# StepperMotor-Shield-ArduinoUNO.net
KiCad netlist of a schematic drawn in EAGLE
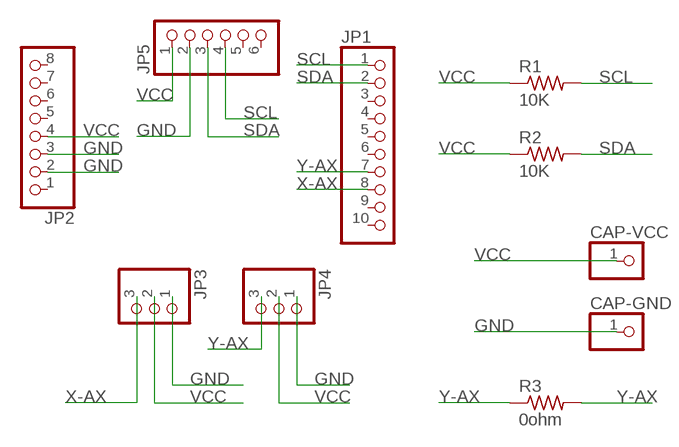
[diagram p0: schematic, sheet 1]

(export (version "E")
  (design (tool "Eeschema 10.0.6"))
  (components
    (comp (ref "CAP-GND")
      (value "PINHD-1X1")
      (footprint "eagle-import:1X01")
      (libsource (lib "eagle-import") (part "PINHD-1X1"))
    )
    (comp (ref "CAP-VCC")
      (value "PINHD-1X1")
      (footprint "eagle-import:1X01")
      (libsource (lib "eagle-import") (part "PINHD-1X1"))
    )
    (comp (ref "JP1")
      (value "PINHD-1X10")
      (footprint "eagle-import:1X10")
      (libsource (lib "eagle-import") (part "PINHD-1X10"))
    )
    (comp (ref "JP2")
      (value "PINHD-1X8")
      (footprint "eagle-import:1X08")
      (libsource (lib "eagle-import") (part "PINHD-1X8"))
    )
    (comp (ref "JP3")
      (value "PINHD-1X3")
      (footprint "eagle-import:1X03")
      (libsource (lib "eagle-import") (part "PINHD-1X3"))
    )
    (comp (ref "JP4")
      (value "PINHD-1X3")
      (footprint "eagle-import:1X03")
      (libsource (lib "eagle-import") (part "PINHD-1X3"))
    )
    (comp (ref "JP5")
      (value "PINHD-1X6")
      (footprint "eagle-import:1X06")
      (libsource (lib "eagle-import") (part "PINHD-1X6"))
    )
    (comp (ref "R1")
      (value "10K")
      (footprint "eagle-import:R1206FAB")
      (libsource (lib "eagle-import") (part "RES-US1206FAB"))
    )
    (comp (ref "R2")
      (value "10K")
      (footprint "eagle-import:R1206FAB")
      (libsource (lib "eagle-import") (part "RES-US1206FAB"))
    )
    (comp (ref "R3")
      (value "0ohm")
      (footprint "eagle-import:R1206FAB")
      (libsource (lib "eagle-import") (part "RES-US1206FAB"))
    )
  )
  (nets
    (net (code "1") (name "/GND") (class "Default")
      (node (ref "CAP-GND") (pin "1") (pinfunction "1_1") (pintype "passive"))
      (node (ref "JP2") (pin "2") (pinfunction "2_2") (pintype "passive"))
      (node (ref "JP2") (pin "3") (pinfunction "3_3") (pintype "passive"))
      (node (ref "JP3") (pin "1") (pinfunction "1_1") (pintype "passive"))
      (node (ref "JP4") (pin "1") (pinfunction "1_1") (pintype "passive"))
      (node (ref "JP5") (pin "2") (pinfunction "2_2") (pintype "passive"))
    )
    (net (code "2") (name "/SCL") (class "Default")
      (node (ref "JP1") (pin "1") (pinfunction "1_1") (pintype "passive"))
      (node (ref "JP5") (pin "4") (pinfunction "4_4") (pintype "passive"))
      (node (ref "R1") (pin "2") (pinfunction "2_2") (pintype "passive"))
    )
    (net (code "3") (name "/SDA") (class "Default")
      (node (ref "JP1") (pin "2") (pinfunction "2_2") (pintype "passive"))
      (node (ref "JP5") (pin "3") (pinfunction "3_3") (pintype "passive"))
      (node (ref "R2") (pin "2") (pinfunction "2_2") (pintype "passive"))
    )
    (net (code "4") (name "/VCC") (class "Default")
      (node (ref "CAP-VCC") (pin "1") (pinfunction "1_1") (pintype "passive"))
      (node (ref "JP2") (pin "4") (pinfunction "4_4") (pintype "passive"))
      (node (ref "JP3") (pin "2") (pinfunction "2_2") (pintype "passive"))
      (node (ref "JP4") (pin "2") (pinfunction "2_2") (pintype "passive"))
      (node (ref "JP5") (pin "1") (pinfunction "1_1") (pintype "passive"))
      (node (ref "R1") (pin "1") (pinfunction "1_1") (pintype "passive"))
      (node (ref "R2") (pin "1") (pinfunction "1_1") (pintype "passive"))
    )
    (net (code "5") (name "/X-AX") (class "Default")
      (node (ref "JP1") (pin "8") (pinfunction "8_8") (pintype "passive"))
      (node (ref "JP3") (pin "3") (pinfunction "3_3") (pintype "passive"))
    )
    (net (code "6") (name "/Y-AX") (class "Default")
      (node (ref "JP1") (pin "7") (pinfunction "7_7") (pintype "passive"))
      (node (ref "JP4") (pin "3") (pinfunction "3_3") (pintype "passive"))
      (node (ref "R3") (pin "1") (pinfunction "1_1") (pintype "passive"))
      (node (ref "R3") (pin "2") (pinfunction "2_2") (pintype "passive"))
    )
    (net (code "7") (name "unconnected-(JP1-Pad3)") (class "Default")
      (node (ref "JP1") (pin "3") (pinfunction "3_3") (pintype "passive"))
    )
    (net (code "8") (name "unconnected-(JP1-Pad4)") (class "Default")
      (node (ref "JP1") (pin "4") (pinfunction "4_4") (pintype "passive"))
    )
    (net (code "9") (name "unconnected-(JP1-Pad5)") (class "Default")
      (node (ref "JP1") (pin "5") (pinfunction "5_5") (pintype "passive"))
    )
    (net (code "10") (name "unconnected-(JP1-Pad6)") (class "Default")
      (node (ref "JP1") (pin "6") (pinfunction "6_6") (pintype "passive"))
    )
    (net (code "11") (name "unconnected-(JP1-Pad9)") (class "Default")
      (node (ref "JP1") (pin "9") (pinfunction "9_9") (pintype "passive"))
    )
    (net (code "12") (name "unconnected-(JP1-Pad10)") (class "Default")
      (node (ref "JP1") (pin "10") (pinfunction "10_10") (pintype "passive"))
    )
    (net (code "13") (name "unconnected-(JP2-Pad1)") (class "Default")
      (node (ref "JP2") (pin "1") (pinfunction "1_1") (pintype "passive"))
    )
    (net (code "14") (name "unconnected-(JP2-Pad5)") (class "Default")
      (node (ref "JP2") (pin "5") (pinfunction "5_5") (pintype "passive"))
    )
    (net (code "15") (name "unconnected-(JP2-Pad6)") (class "Default")
      (node (ref "JP2") (pin "6") (pinfunction "6_6") (pintype "passive"))
    )
    (net (code "16") (name "unconnected-(JP2-Pad7)") (class "Default")
      (node (ref "JP2") (pin "7") (pinfunction "7_7") (pintype "passive"))
    )
    (net (code "17") (name "unconnected-(JP2-Pad8)") (class "Default")
      (node (ref "JP2") (pin "8") (pinfunction "8_8") (pintype "passive"))
    )
    (net (code "18") (name "unconnected-(JP5-Pad5)") (class "Default")
      (node (ref "JP5") (pin "5") (pinfunction "5_5") (pintype "passive"))
    )
    (net (code "19") (name "unconnected-(JP5-Pad6)") (class "Default")
      (node (ref "JP5") (pin "6") (pinfunction "6_6") (pintype "passive"))
    )
  )
)
